# Enable_Signals.net
KiCad netlist of a schematic drawn in Altium Designer
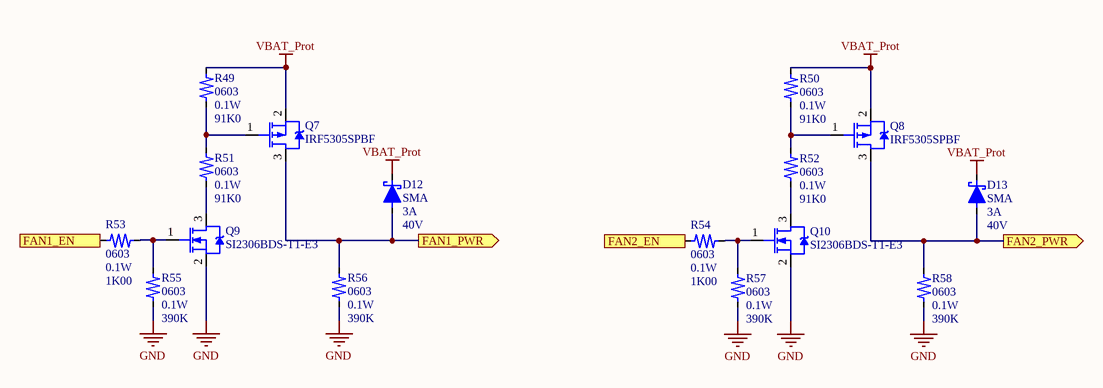
[diagram p0: Enable_Signals.SchDoc]

(export (version "E")
  (design (tool "Eeschema 10.0.6"))
  (components
    (comp (ref "D12")
      (value "SMA")
      (footprint "SMA")
      (fields
        (field (name "PART NUMBER") "SS34A")
        (field (name "RATING") "3A")
        (field (name "ALTIUM_VALUE") "40V")
      )
      (libsource (lib "Components") (part "Diode_Schottky"))
    )
    (comp (ref "D13")
      (value "SMA")
      (footprint "SMA")
      (fields
        (field (name "PART NUMBER") "SS34A")
        (field (name "RATING") "3A")
        (field (name "ALTIUM_VALUE") "40V")
      )
      (libsource (lib "Components") (part "Diode_Schottky"))
    )
    (comp (ref "Q7")
      (value "IRF5305SPBF")
      (footprint "D2PAK-2")
      (description "P-Channel Power MOSFET")
      (libsource (lib "Components") (part "Transistor_P-FET"))
    )
    (comp (ref "Q8")
      (value "IRF5305SPBF")
      (footprint "D2PAK-2")
      (description "P-Channel Power MOSFET")
      (libsource (lib "Components") (part "Transistor_P-FET"))
    )
    (comp (ref "Q9")
      (value "SI2306BDS-T1-E3")
      (footprint "SOT-23-3")
      (description "N-Channel Power MOSFET")
      (libsource (lib "Components") (part "Transistor_N-FET"))
    )
    (comp (ref "Q10")
      (value "SI2306BDS-T1-E3")
      (footprint "SOT-23-3")
      (description "N-Channel Power MOSFET")
      (libsource (lib "Components") (part "Transistor_N-FET"))
    )
    (comp (ref "R49")
      (value "0603")
      (footprint "R_0603")
      (fields
        (field (name "TOLERANCE") "1%")
        (field (name "PART NUMBER") "CR-03FL7---91K")
        (field (name "RATING") "0.1W")
        (field (name "ALTIUM_VALUE") "91K0")
        (field (name "NI PART NUMBER") "612775-01")
      )
      (libsource (lib "Components") (part "Resistor_Chip"))
    )
    (comp (ref "R50")
      (value "0603")
      (footprint "R_0603")
      (fields
        (field (name "TOLERANCE") "1%")
        (field (name "PART NUMBER") "CR-03FL7---91K")
        (field (name "RATING") "0.1W")
        (field (name "ALTIUM_VALUE") "91K0")
        (field (name "NI PART NUMBER") "612775-01")
      )
      (libsource (lib "Components") (part "Resistor_Chip"))
    )
    (comp (ref "R51")
      (value "0603")
      (footprint "R_0603")
      (fields
        (field (name "TOLERANCE") "1%")
        (field (name "PART NUMBER") "CR-03FL7---91K")
        (field (name "RATING") "0.1W")
        (field (name "ALTIUM_VALUE") "91K0")
        (field (name "NI PART NUMBER") "612775-01")
      )
      (libsource (lib "Components") (part "Resistor_Chip"))
    )
    (comp (ref "R52")
      (value "0603")
      (footprint "R_0603")
      (fields
        (field (name "TOLERANCE") "1%")
        (field (name "PART NUMBER") "CR-03FL7---91K")
        (field (name "RATING") "0.1W")
        (field (name "ALTIUM_VALUE") "91K0")
        (field (name "NI PART NUMBER") "612775-01")
      )
      (libsource (lib "Components") (part "Resistor_Chip"))
    )
    (comp (ref "R53")
      (value "0603")
      (footprint "R_0603")
      (fields
        (field (name "TOLERANCE") "1%")
        (field (name "PART NUMBER") "CR-03FL7----1K")
        (field (name "RATING") "0.1W")
        (field (name "ALTIUM_VALUE") "1K00")
        (field (name "NI PART NUMBER") "713776-01")
      )
      (libsource (lib "Components") (part "Resistor_Chip"))
    )
    (comp (ref "R54")
      (value "0603")
      (footprint "R_0603")
      (fields
        (field (name "TOLERANCE") "1%")
        (field (name "PART NUMBER") "CR-03FL7----1K")
        (field (name "RATING") "0.1W")
        (field (name "ALTIUM_VALUE") "1K00")
        (field (name "NI PART NUMBER") "713776-01")
      )
      (libsource (lib "Components") (part "Resistor_Chip"))
    )
    (comp (ref "R55")
      (value "0603")
      (footprint "R_0603")
      (fields
        (field (name "TOLERANCE") "1%")
        (field (name "PART NUMBER") "CR-03FL7--390K")
        (field (name "RATING") "0.1W")
        (field (name "ALTIUM_VALUE") "390K")
      )
      (libsource (lib "Components") (part "Resistor_Chip"))
    )
    (comp (ref "R56")
      (value "0603")
      (footprint "R_0603")
      (fields
        (field (name "TOLERANCE") "1%")
        (field (name "PART NUMBER") "CR-03FL7--390K")
        (field (name "RATING") "0.1W")
        (field (name "ALTIUM_VALUE") "390K")
      )
      (libsource (lib "Components") (part "Resistor_Chip"))
    )
    (comp (ref "R57")
      (value "0603")
      (footprint "R_0603")
      (fields
        (field (name "TOLERANCE") "1%")
        (field (name "PART NUMBER") "CR-03FL7--390K")
        (field (name "RATING") "0.1W")
        (field (name "ALTIUM_VALUE") "390K")
      )
      (libsource (lib "Components") (part "Resistor_Chip"))
    )
    (comp (ref "R58")
      (value "0603")
      (footprint "R_0603")
      (fields
        (field (name "TOLERANCE") "1%")
        (field (name "PART NUMBER") "CR-03FL7--390K")
        (field (name "RATING") "0.1W")
        (field (name "ALTIUM_VALUE") "390K")
      )
      (libsource (lib "Components") (part "Resistor_Chip"))
    )
  )
  (nets
    (net (code "1") (name "/FAN1_EN") (class "Default")
      (node (ref "R53") (pin "1") (pinfunction "R1_1") (pintype "passive"))
    )
    (net (code "2") (name "/FAN1_PWR") (class "Default")
      (node (ref "D12") (pin "2") (pinfunction "DA_2") (pintype "passive"))
      (node (ref "Q7") (pin "3") (pinfunction "D_3") (pintype "passive"))
      (node (ref "R56") (pin "2") (pinfunction "R2_2") (pintype "passive"))
    )
    (net (code "3") (name "/FAN2_EN") (class "Default")
      (node (ref "R54") (pin "1") (pinfunction "R1_1") (pintype "passive"))
    )
    (net (code "4") (name "/FAN2_PWR") (class "Default")
      (node (ref "D13") (pin "2") (pinfunction "DA_2") (pintype "passive"))
      (node (ref "Q8") (pin "3") (pinfunction "D_3") (pintype "passive"))
      (node (ref "R58") (pin "2") (pinfunction "R2_2") (pintype "passive"))
    )
    (net (code "5") (name "GND") (class "Default")
      (node (ref "Q10") (pin "2") (pinfunction "S_2") (pintype "passive"))
      (node (ref "Q9") (pin "2") (pinfunction "S_2") (pintype "passive"))
      (node (ref "R55") (pin "1") (pinfunction "R1_1") (pintype "passive"))
      (node (ref "R56") (pin "1") (pinfunction "R1_1") (pintype "passive"))
      (node (ref "R57") (pin "1") (pinfunction "R1_1") (pintype "passive"))
      (node (ref "R58") (pin "1") (pinfunction "R1_1") (pintype "passive"))
    )
    (net (code "6") (name "Net-(Q7-G)") (class "Default")
      (node (ref "Q7") (pin "1") (pinfunction "G_1") (pintype "passive"))
      (node (ref "R49") (pin "1") (pinfunction "R1_1") (pintype "passive"))
      (node (ref "R51") (pin "2") (pinfunction "R2_2") (pintype "passive"))
    )
    (net (code "7") (name "Net-(Q8-G)") (class "Default")
      (node (ref "Q8") (pin "1") (pinfunction "G_1") (pintype "passive"))
      (node (ref "R50") (pin "1") (pinfunction "R1_1") (pintype "passive"))
      (node (ref "R52") (pin "2") (pinfunction "R2_2") (pintype "passive"))
    )
    (net (code "8") (name "Net-(Q9-D)") (class "Default")
      (node (ref "Q9") (pin "3") (pinfunction "D_3") (pintype "passive"))
      (node (ref "R51") (pin "1") (pinfunction "R1_1") (pintype "passive"))
    )
    (net (code "9") (name "Net-(Q9-G)") (class "Default")
      (node (ref "Q9") (pin "1") (pinfunction "G_1") (pintype "passive"))
      (node (ref "R53") (pin "2") (pinfunction "R2_2") (pintype "passive"))
      (node (ref "R55") (pin "2") (pinfunction "R2_2") (pintype "passive"))
    )
    (net (code "10") (name "Net-(Q10-D)") (class "Default")
      (node (ref "Q10") (pin "3") (pinfunction "D_3") (pintype "passive"))
      (node (ref "R52") (pin "1") (pinfunction "R1_1") (pintype "passive"))
    )
    (net (code "11") (name "Net-(Q10-G)") (class "Default")
      (node (ref "Q10") (pin "1") (pinfunction "G_1") (pintype "passive"))
      (node (ref "R54") (pin "2") (pinfunction "R2_2") (pintype "passive"))
      (node (ref "R57") (pin "2") (pinfunction "R2_2") (pintype "passive"))
    )
    (net (code "12") (name "VBAT_Prot") (class "Default")
      (node (ref "D12") (pin "1") (pinfunction "DC_1") (pintype "passive"))
      (node (ref "D13") (pin "1") (pinfunction "DC_1") (pintype "passive"))
      (node (ref "Q7") (pin "2") (pinfunction "S_2") (pintype "passive"))
      (node (ref "Q8") (pin "2") (pinfunction "S_2") (pintype "passive"))
      (node (ref "R49") (pin "2") (pinfunction "R2_2") (pintype "passive"))
      (node (ref "R50") (pin "2") (pinfunction "R2_2") (pintype "passive"))
    )
  )
)
